# SH8_-_CAN.net
KiCad netlist of a schematic drawn in Altium Designer
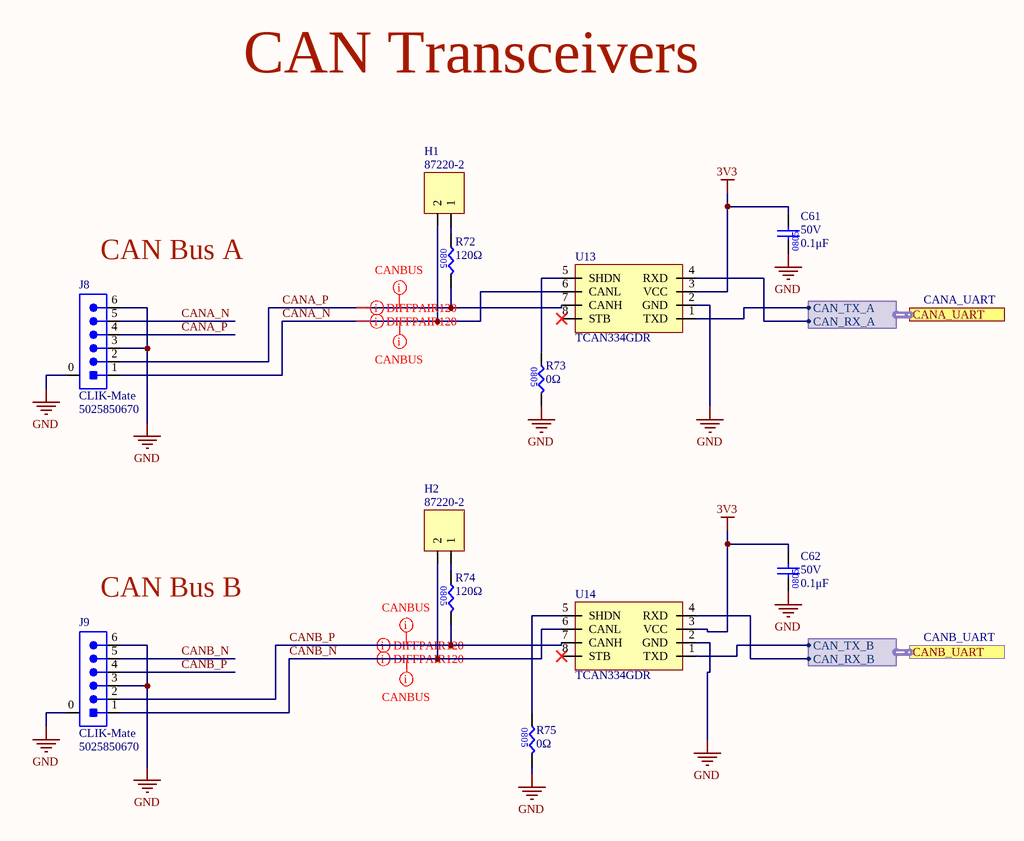
[diagram p0: SH8 - CAN.SchDoc]

(export (version "E")
  (design (tool "Eeschema 10.0.6"))
  (components
    (comp (ref "C61")
      (value "0.1μF")
      (footprint "CAP2012")
      (description "CAP CER 0.1UF 50V X7R 0805")
      (fields
        (field (name "VOLTAGE RATING") "50V")
        (field (name "LCSC PART #") "C49678")
        (field (name "Comment") "CAP_0.1uF_50V_0805")
      )
      (libsource (lib "UWRT_Schematic_Library_2020") (part "CAP_0.1uF_50V_0805"))
    )
    (comp (ref "C62")
      (value "0.1μF")
      (footprint "CAP2012")
      (description "CAP CER 0.1UF 50V X7R 0805")
      (fields
        (field (name "VOLTAGE RATING") "50V")
        (field (name "LCSC PART #") "C49678")
        (field (name "Comment") "CAP_0.1uF_50V_0805")
      )
      (libsource (lib "UWRT_Schematic_Library_2020") (part "CAP_0.1uF_50V_0805"))
    )
    (comp (ref "H1")
      (value "JUMPER_2")
      (footprint "HDR1X2")
      (description "HEADER 2X1")
      (fields (field (name "MANUFACTURER PART NUMBER 1") "87220-2"))
      (libsource (lib "UWRT_Schematic_Library_2020") (part "JUMPER_2"))
    )
    (comp (ref "H2")
      (value "JUMPER_2")
      (footprint "HDR1X2")
      (description "HEADER 2X1")
      (fields (field (name "MANUFACTURER PART NUMBER 1") "87220-2"))
      (libsource (lib "UWRT_Schematic_Library_2020") (part "JUMPER_2"))
    )
    (comp (ref "J8")
      (value "CON_6M_SM_RA_1.5mm")
      (footprint "MOLEX-5025850670")
      (description "CONN HEADER SMD RIGHT ANGLE 1.5 MM PITCH")
      (fields (field (name "FAMILY") "CLIK-Mate") (field (name "MANUFACTURER PART NUMBER 1") "5025850670"))
      (libsource (lib "UWRT_Schematic_Library_2020") (part "CON_6M_SM_RA_1.5mm"))
    )
    (comp (ref "J9")
      (value "CON_6M_SM_RA_1.5mm")
      (footprint "MOLEX-5025850670")
      (description "CONN HEADER SMD RIGHT ANGLE 1.5 MM PITCH")
      (fields (field (name "FAMILY") "CLIK-Mate") (field (name "MANUFACTURER PART NUMBER 1") "5025850670"))
      (libsource (lib "UWRT_Schematic_Library_2020") (part "CON_6M_SM_RA_1.5mm"))
    )
    (comp (ref "R72")
      (value "120Ω")
      (footprint "RES0805")
      (description "RES 120 OHM 1% 1/8W 0805")
      (fields (field (name "LCSC PART #") "C17437") (field (name "Comment") "RES_120Ω_0805_1%"))
      (libsource (lib "UWRT_Schematic_Library_2020") (part "RES_120Ω_0805_1%"))
    )
    (comp (ref "R73")
      (value "0Ω")
      (footprint "RES0805")
      (description "RES 0 OHM JUMPER 1/8W 0805")
      (fields (field (name "LCSC PART #") "C17477") (field (name "Comment") "RES_0Ω_0805"))
      (libsource (lib "UWRT_Schematic_Library_2020") (part "RES_0Ω_0805"))
    )
    (comp (ref "R74")
      (value "120Ω")
      (footprint "RES0805")
      (description "RES 120 OHM 1% 1/8W 0805")
      (fields (field (name "LCSC PART #") "C17437") (field (name "Comment") "RES_120Ω_0805_1%"))
      (libsource (lib "UWRT_Schematic_Library_2020") (part "RES_120Ω_0805_1%"))
    )
    (comp (ref "R75")
      (value "0Ω")
      (footprint "RES0805")
      (description "RES 0 OHM JUMPER 1/8W 0805")
      (fields (field (name "LCSC PART #") "C17477") (field (name "Comment") "RES_0Ω_0805"))
      (libsource (lib "UWRT_Schematic_Library_2020") (part "RES_0Ω_0805"))
    )
    (comp (ref "U13")
      (value "IC_CAN_TRANSCEIVER")
      (footprint "SOIC127P600X175-8N")
      (description "IC TRANSCEIVER 1/1 8SOIC")
      (fields (field (name "MANUFACTURER PART NUMBER 1") "TCAN334GDR"))
      (libsource (lib "UWRT_Schematic_Library_2020") (part "IC_CAN_TRANSCEIVER"))
    )
    (comp (ref "U14")
      (value "IC_CAN_TRANSCEIVER")
      (footprint "SOIC127P600X175-8N")
      (description "IC TRANSCEIVER 1/1 8SOIC")
      (fields (field (name "MANUFACTURER PART NUMBER 1") "TCAN334GDR"))
      (libsource (lib "UWRT_Schematic_Library_2020") (part "IC_CAN_TRANSCEIVER"))
    )
  )
  (nets
    (net (code "3") (name "/CANA_N") (class "Default")
      (node (ref "H1") (pin "2") (pinfunction "2_2") (pintype "passive"))
      (node (ref "J8") (pin "1") (pinfunction "1_1") (pintype "passive"))
      (node (ref "J8") (pin "5") (pinfunction "5_5") (pintype "passive"))
      (node (ref "U13") (pin "6") (pinfunction "CANL_6") (pintype "passive"))
    )
    (net (code "4") (name "/CANA_P") (class "Default")
      (node (ref "J8") (pin "2") (pinfunction "2_2") (pintype "passive"))
      (node (ref "J8") (pin "4") (pinfunction "4_4") (pintype "passive"))
      (node (ref "R72") (pin "2") (pinfunction "2_2") (pintype "passive"))
      (node (ref "U13") (pin "7") (pinfunction "CANH_7") (pintype "passive"))
    )
    (net (code "5") (name "/CANB_N") (class "Default")
      (node (ref "H2") (pin "2") (pinfunction "2_2") (pintype "passive"))
      (node (ref "J9") (pin "1") (pinfunction "1_1") (pintype "passive"))
      (node (ref "J9") (pin "5") (pinfunction "5_5") (pintype "passive"))
      (node (ref "U14") (pin "6") (pinfunction "CANL_6") (pintype "passive"))
    )
    (net (code "6") (name "/CANB_P") (class "Default")
      (node (ref "J9") (pin "2") (pinfunction "2_2") (pintype "passive"))
      (node (ref "J9") (pin "4") (pinfunction "4_4") (pintype "passive"))
      (node (ref "R74") (pin "2") (pinfunction "2_2") (pintype "passive"))
      (node (ref "U14") (pin "7") (pinfunction "CANH_7") (pintype "passive"))
    )
    (net (code "7") (name "/CAN_RX_A") (class "Default")
      (node (ref "U13") (pin "4") (pinfunction "RXD_4") (pintype "passive"))
    )
    (net (code "8") (name "/CAN_RX_B") (class "Default")
      (node (ref "U14") (pin "4") (pinfunction "RXD_4") (pintype "passive"))
    )
    (net (code "9") (name "/CAN_TX_A") (class "Default")
      (node (ref "U13") (pin "1") (pinfunction "TXD_1") (pintype "passive"))
    )
    (net (code "10") (name "/CAN_TX_B") (class "Default")
      (node (ref "U14") (pin "1") (pinfunction "TXD_1") (pintype "passive"))
    )
    (net (code "13") (name "3V3") (class "Default")
      (node (ref "C61") (pin "2") (pinfunction "2_2") (pintype "passive"))
      (node (ref "C62") (pin "2") (pinfunction "2_2") (pintype "passive"))
      (node (ref "U13") (pin "3") (pinfunction "VCC_3") (pintype "passive"))
      (node (ref "U14") (pin "3") (pinfunction "VCC_3") (pintype "passive"))
    )
    (net (code "14") (name "GND") (class "Default")
      (node (ref "C61") (pin "1") (pinfunction "1_1") (pintype "passive"))
      (node (ref "C62") (pin "1") (pinfunction "1_1") (pintype "passive"))
      (node (ref "J8") (pin "0") (pinfunction "0_0") (pintype "passive"))
      (node (ref "J8") (pin "3") (pinfunction "3_3") (pintype "passive"))
      (node (ref "J8") (pin "6") (pinfunction "6_6") (pintype "passive"))
      (node (ref "J9") (pin "0") (pinfunction "0_0") (pintype "passive"))
      (node (ref "J9") (pin "3") (pinfunction "3_3") (pintype "passive"))
      (node (ref "J9") (pin "6") (pinfunction "6_6") (pintype "passive"))
      (node (ref "R73") (pin "2") (pinfunction "2_2") (pintype "passive"))
      (node (ref "R75") (pin "2") (pinfunction "2_2") (pintype "passive"))
      (node (ref "U13") (pin "2") (pinfunction "GND_2") (pintype "passive"))
      (node (ref "U14") (pin "2") (pinfunction "GND_2") (pintype "passive"))
    )
    (net (code "15") (name "Net-(H1-Pad1)") (class "Default")
      (node (ref "H1") (pin "1") (pinfunction "1_1") (pintype "passive"))
      (node (ref "R72") (pin "1") (pinfunction "1_1") (pintype "passive"))
    )
    (net (code "16") (name "Net-(H2-Pad1)") (class "Default")
      (node (ref "H2") (pin "1") (pinfunction "1_1") (pintype "passive"))
      (node (ref "R74") (pin "1") (pinfunction "1_1") (pintype "passive"))
    )
    (net (code "17") (name "Net-(U13-SHDN)") (class "Default")
      (node (ref "R73") (pin "1") (pinfunction "1_1") (pintype "passive"))
      (node (ref "U13") (pin "5") (pinfunction "SHDN_5") (pintype "passive"))
    )
    (net (code "18") (name "Net-(U14-SHDN)") (class "Default")
      (node (ref "R75") (pin "1") (pinfunction "1_1") (pintype "passive"))
      (node (ref "U14") (pin "5") (pinfunction "SHDN_5") (pintype "passive"))
    )
    (net (code "19") (name "unconnected-(U13-STB-Pad8)") (class "Default")
      (node (ref "U13") (pin "8") (pinfunction "STB_8") (pintype "passive+no_connect"))
    )
    (net (code "20") (name "unconnected-(U14-STB-Pad8)") (class "Default")
      (node (ref "U14") (pin "8") (pinfunction "STB_8") (pintype "passive+no_connect"))
    )
  )
)
